# top_prog.net
KiCad netlist of a schematic drawn in EAGLE
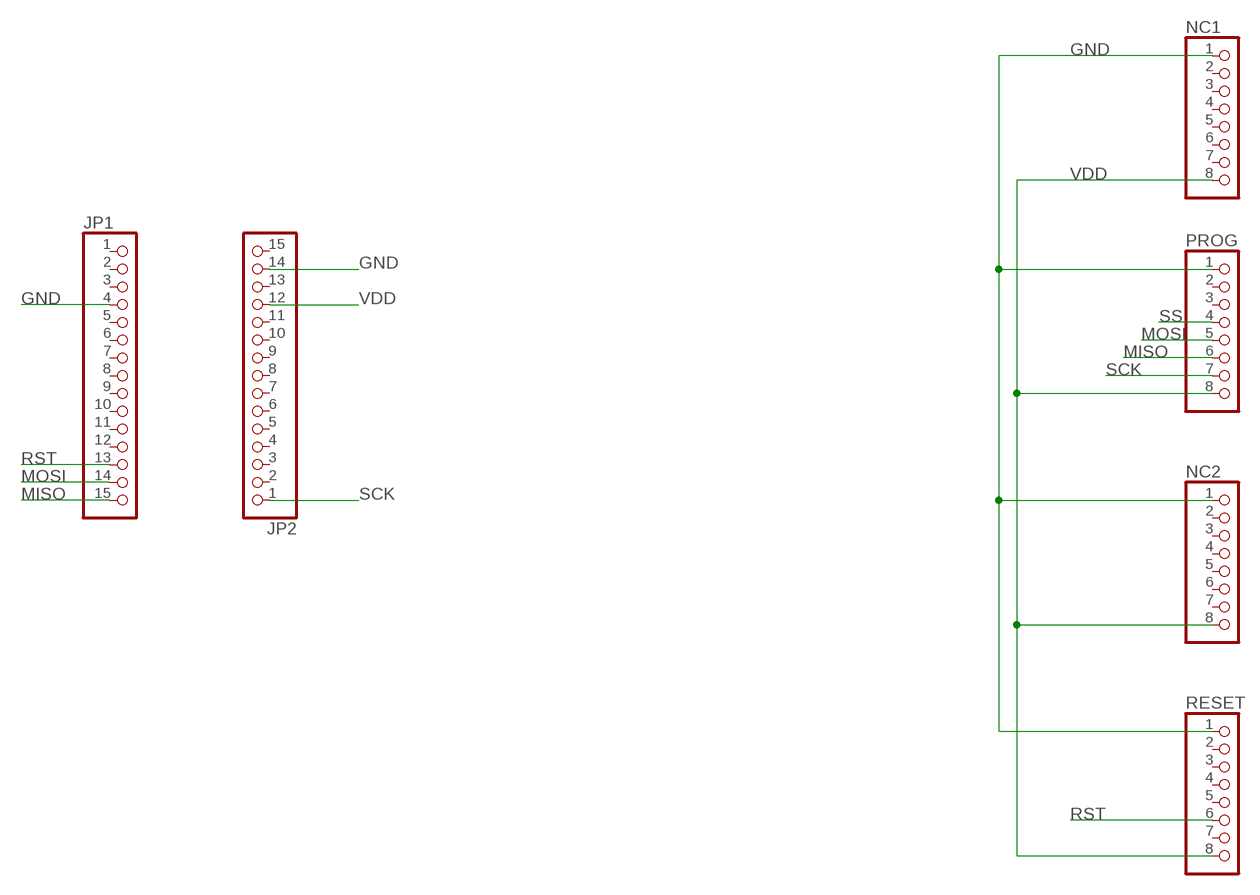
[diagram p0: schematic, sheet 1]

(export (version "E")
  (design (tool "Eeschema 10.0.6"))
  (components
    (comp (ref "JP1")
      (value "PINHD-1X15")
      (footprint "eagle-import:1X15")
      (libsource (lib "eagle-import") (part "PINHD-1X15"))
    )
    (comp (ref "JP2")
      (value "PINHD-1X15")
      (footprint "eagle-import:1X15")
      (libsource (lib "eagle-import") (part "PINHD-1X15"))
    )
    (comp (ref "NC1")
      (value "PINHD-1X8")
      (footprint "eagle-import:1X08")
      (libsource (lib "eagle-import") (part "PINHD-1X8"))
    )
    (comp (ref "NC2")
      (value "PINHD-1X8")
      (footprint "eagle-import:1X08")
      (libsource (lib "eagle-import") (part "PINHD-1X8"))
    )
    (comp (ref "PROG")
      (value "PINHD-1X8")
      (footprint "eagle-import:1X08")
      (libsource (lib "eagle-import") (part "PINHD-1X8"))
    )
    (comp (ref "RESET")
      (value "PINHD-1X8")
      (footprint "eagle-import:1X08")
      (libsource (lib "eagle-import") (part "PINHD-1X8"))
    )
  )
  (nets
    (net (code "1") (name "/GND") (class "Default")
      (node (ref "JP1") (pin "4") (pinfunction "4_4") (pintype "passive"))
      (node (ref "JP2") (pin "14") (pinfunction "14_14") (pintype "passive"))
      (node (ref "NC1") (pin "1") (pinfunction "1_1") (pintype "passive"))
      (node (ref "NC2") (pin "1") (pinfunction "1_1") (pintype "passive"))
      (node (ref "PROG") (pin "1") (pinfunction "1_1") (pintype "passive"))
      (node (ref "RESET") (pin "1") (pinfunction "1_1") (pintype "passive"))
    )
    (net (code "2") (name "/MISO") (class "Default")
      (node (ref "JP1") (pin "15") (pinfunction "15_15") (pintype "passive"))
      (node (ref "PROG") (pin "6") (pinfunction "6_6") (pintype "passive"))
    )
    (net (code "3") (name "/MOSI") (class "Default")
      (node (ref "JP1") (pin "14") (pinfunction "14_14") (pintype "passive"))
      (node (ref "PROG") (pin "5") (pinfunction "5_5") (pintype "passive"))
    )
    (net (code "4") (name "/RST") (class "Default")
      (node (ref "JP1") (pin "13") (pinfunction "13_13") (pintype "passive"))
      (node (ref "RESET") (pin "6") (pinfunction "6_6") (pintype "passive"))
    )
    (net (code "5") (name "/SCK") (class "Default")
      (node (ref "JP2") (pin "1") (pinfunction "1_1") (pintype "passive"))
      (node (ref "PROG") (pin "7") (pinfunction "7_7") (pintype "passive"))
    )
    (net (code "6") (name "/SS") (class "Default")
      (node (ref "PROG") (pin "4") (pinfunction "4_4") (pintype "passive"))
    )
    (net (code "7") (name "/VDD") (class "Default")
      (node (ref "JP2") (pin "12") (pinfunction "12_12") (pintype "passive"))
      (node (ref "NC1") (pin "8") (pinfunction "8_8") (pintype "passive"))
      (node (ref "NC2") (pin "8") (pinfunction "8_8") (pintype "passive"))
      (node (ref "PROG") (pin "8") (pinfunction "8_8") (pintype "passive"))
      (node (ref "RESET") (pin "8") (pinfunction "8_8") (pintype "passive"))
    )
    (net (code "8") (name "unconnected-(JP1-Pad1)") (class "Default")
      (node (ref "JP1") (pin "1") (pinfunction "1_1") (pintype "passive"))
    )
    (net (code "9") (name "unconnected-(JP1-Pad2)") (class "Default")
      (node (ref "JP1") (pin "2") (pinfunction "2_2") (pintype "passive"))
    )
    (net (code "10") (name "unconnected-(JP1-Pad3)") (class "Default")
      (node (ref "JP1") (pin "3") (pinfunction "3_3") (pintype "passive"))
    )
    (net (code "11") (name "unconnected-(JP1-Pad5)") (class "Default")
      (node (ref "JP1") (pin "5") (pinfunction "5_5") (pintype "passive"))
    )
    (net (code "12") (name "unconnected-(JP1-Pad6)") (class "Default")
      (node (ref "JP1") (pin "6") (pinfunction "6_6") (pintype "passive"))
    )
    (net (code "13") (name "unconnected-(JP1-Pad7)") (class "Default")
      (node (ref "JP1") (pin "7") (pinfunction "7_7") (pintype "passive"))
    )
    (net (code "14") (name "unconnected-(JP1-Pad8)") (class "Default")
      (node (ref "JP1") (pin "8") (pinfunction "8_8") (pintype "passive"))
    )
    (net (code "15") (name "unconnected-(JP1-Pad9)") (class "Default")
      (node (ref "JP1") (pin "9") (pinfunction "9_9") (pintype "passive"))
    )
    (net (code "16") (name "unconnected-(JP1-Pad10)") (class "Default")
      (node (ref "JP1") (pin "10") (pinfunction "10_10") (pintype "passive"))
    )
    (net (code "17") (name "unconnected-(JP1-Pad11)") (class "Default")
      (node (ref "JP1") (pin "11") (pinfunction "11_11") (pintype "passive"))
    )
    (net (code "18") (name "unconnected-(JP1-Pad12)") (class "Default")
      (node (ref "JP1") (pin "12") (pinfunction "12_12") (pintype "passive"))
    )
    (net (code "19") (name "unconnected-(JP2-Pad2)") (class "Default")
      (node (ref "JP2") (pin "2") (pinfunction "2_2") (pintype "passive"))
    )
    (net (code "20") (name "unconnected-(JP2-Pad3)") (class "Default")
      (node (ref "JP2") (pin "3") (pinfunction "3_3") (pintype "passive"))
    )
    (net (code "21") (name "unconnected-(JP2-Pad4)") (class "Default")
      (node (ref "JP2") (pin "4") (pinfunction "4_4") (pintype "passive"))
    )
    (net (code "22") (name "unconnected-(JP2-Pad5)") (class "Default")
      (node (ref "JP2") (pin "5") (pinfunction "5_5") (pintype "passive"))
    )
    (net (code "23") (name "unconnected-(JP2-Pad6)") (class "Default")
      (node (ref "JP2") (pin "6") (pinfunction "6_6") (pintype "passive"))
    )
    (net (code "24") (name "unconnected-(JP2-Pad7)") (class "Default")
      (node (ref "JP2") (pin "7") (pinfunction "7_7") (pintype "passive"))
    )
    (net (code "25") (name "unconnected-(JP2-Pad8)") (class "Default")
      (node (ref "JP2") (pin "8") (pinfunction "8_8") (pintype "passive"))
    )
    (net (code "26") (name "unconnected-(JP2-Pad9)") (class "Default")
      (node (ref "JP2") (pin "9") (pinfunction "9_9") (pintype "passive"))
    )
    (net (code "27") (name "unconnected-(JP2-Pad10)") (class "Default")
      (node (ref "JP2") (pin "10") (pinfunction "10_10") (pintype "passive"))
    )
    (net (code "28") (name "unconnected-(JP2-Pad11)") (class "Default")
      (node (ref "JP2") (pin "11") (pinfunction "11_11") (pintype "passive"))
    )
    (net (code "29") (name "unconnected-(JP2-Pad13)") (class "Default")
      (node (ref "JP2") (pin "13") (pinfunction "13_13") (pintype "passive"))
    )
    (net (code "30") (name "unconnected-(JP2-Pad15)") (class "Default")
      (node (ref "JP2") (pin "15") (pinfunction "15_15") (pintype "passive"))
    )
    (net (code "31") (name "unconnected-(NC1-Pad2)") (class "Default")
      (node (ref "NC1") (pin "2") (pinfunction "2_2") (pintype "passive"))
    )
    (net (code "32") (name "unconnected-(NC1-Pad3)") (class "Default")
      (node (ref "NC1") (pin "3") (pinfunction "3_3") (pintype "passive"))
    )
    (net (code "33") (name "unconnected-(NC1-Pad4)") (class "Default")
      (node (ref "NC1") (pin "4") (pinfunction "4_4") (pintype "passive"))
    )
    (net (code "34") (name "unconnected-(NC1-Pad5)") (class "Default")
      (node (ref "NC1") (pin "5") (pinfunction "5_5") (pintype "passive"))
    )
    (net (code "35") (name "unconnected-(NC1-Pad6)") (class "Default")
      (node (ref "NC1") (pin "6") (pinfunction "6_6") (pintype "passive"))
    )
    (net (code "36") (name "unconnected-(NC1-Pad7)") (class "Default")
      (node (ref "NC1") (pin "7") (pinfunction "7_7") (pintype "passive"))
    )
    (net (code "37") (name "unconnected-(NC2-Pad2)") (class "Default")
      (node (ref "NC2") (pin "2") (pinfunction "2_2") (pintype "passive"))
    )
    (net (code "38") (name "unconnected-(NC2-Pad3)") (class "Default")
      (node (ref "NC2") (pin "3") (pinfunction "3_3") (pintype "passive"))
    )
    (net (code "39") (name "unconnected-(NC2-Pad4)") (class "Default")
      (node (ref "NC2") (pin "4") (pinfunction "4_4") (pintype "passive"))
    )
    (net (code "40") (name "unconnected-(NC2-Pad5)") (class "Default")
      (node (ref "NC2") (pin "5") (pinfunction "5_5") (pintype "passive"))
    )
    (net (code "41") (name "unconnected-(NC2-Pad6)") (class "Default")
      (node (ref "NC2") (pin "6") (pinfunction "6_6") (pintype "passive"))
    )
    (net (code "42") (name "unconnected-(NC2-Pad7)") (class "Default")
      (node (ref "NC2") (pin "7") (pinfunction "7_7") (pintype "passive"))
    )
    (net (code "43") (name "unconnected-(PROG-Pad2)") (class "Default")
      (node (ref "PROG") (pin "2") (pinfunction "2_2") (pintype "passive"))
    )
    (net (code "44") (name "unconnected-(PROG-Pad3)") (class "Default")
      (node (ref "PROG") (pin "3") (pinfunction "3_3") (pintype "passive"))
    )
    (net (code "45") (name "unconnected-(RESET-Pad2)") (class "Default")
      (node (ref "RESET") (pin "2") (pinfunction "2_2") (pintype "passive"))
    )
    (net (code "46") (name "unconnected-(RESET-Pad3)") (class "Default")
      (node (ref "RESET") (pin "3") (pinfunction "3_3") (pintype "passive"))
    )
    (net (code "47") (name "unconnected-(RESET-Pad4)") (class "Default")
      (node (ref "RESET") (pin "4") (pinfunction "4_4") (pintype "passive"))
    )
    (net (code "48") (name "unconnected-(RESET-Pad5)") (class "Default")
      (node (ref "RESET") (pin "5") (pinfunction "5_5") (pintype "passive"))
    )
    (net (code "49") (name "unconnected-(RESET-Pad7)") (class "Default")
      (node (ref "RESET") (pin "7") (pinfunction "7_7") (pintype "passive"))
    )
  )
)
